# Communication.net
KiCad netlist of a schematic drawn in Altium Designer
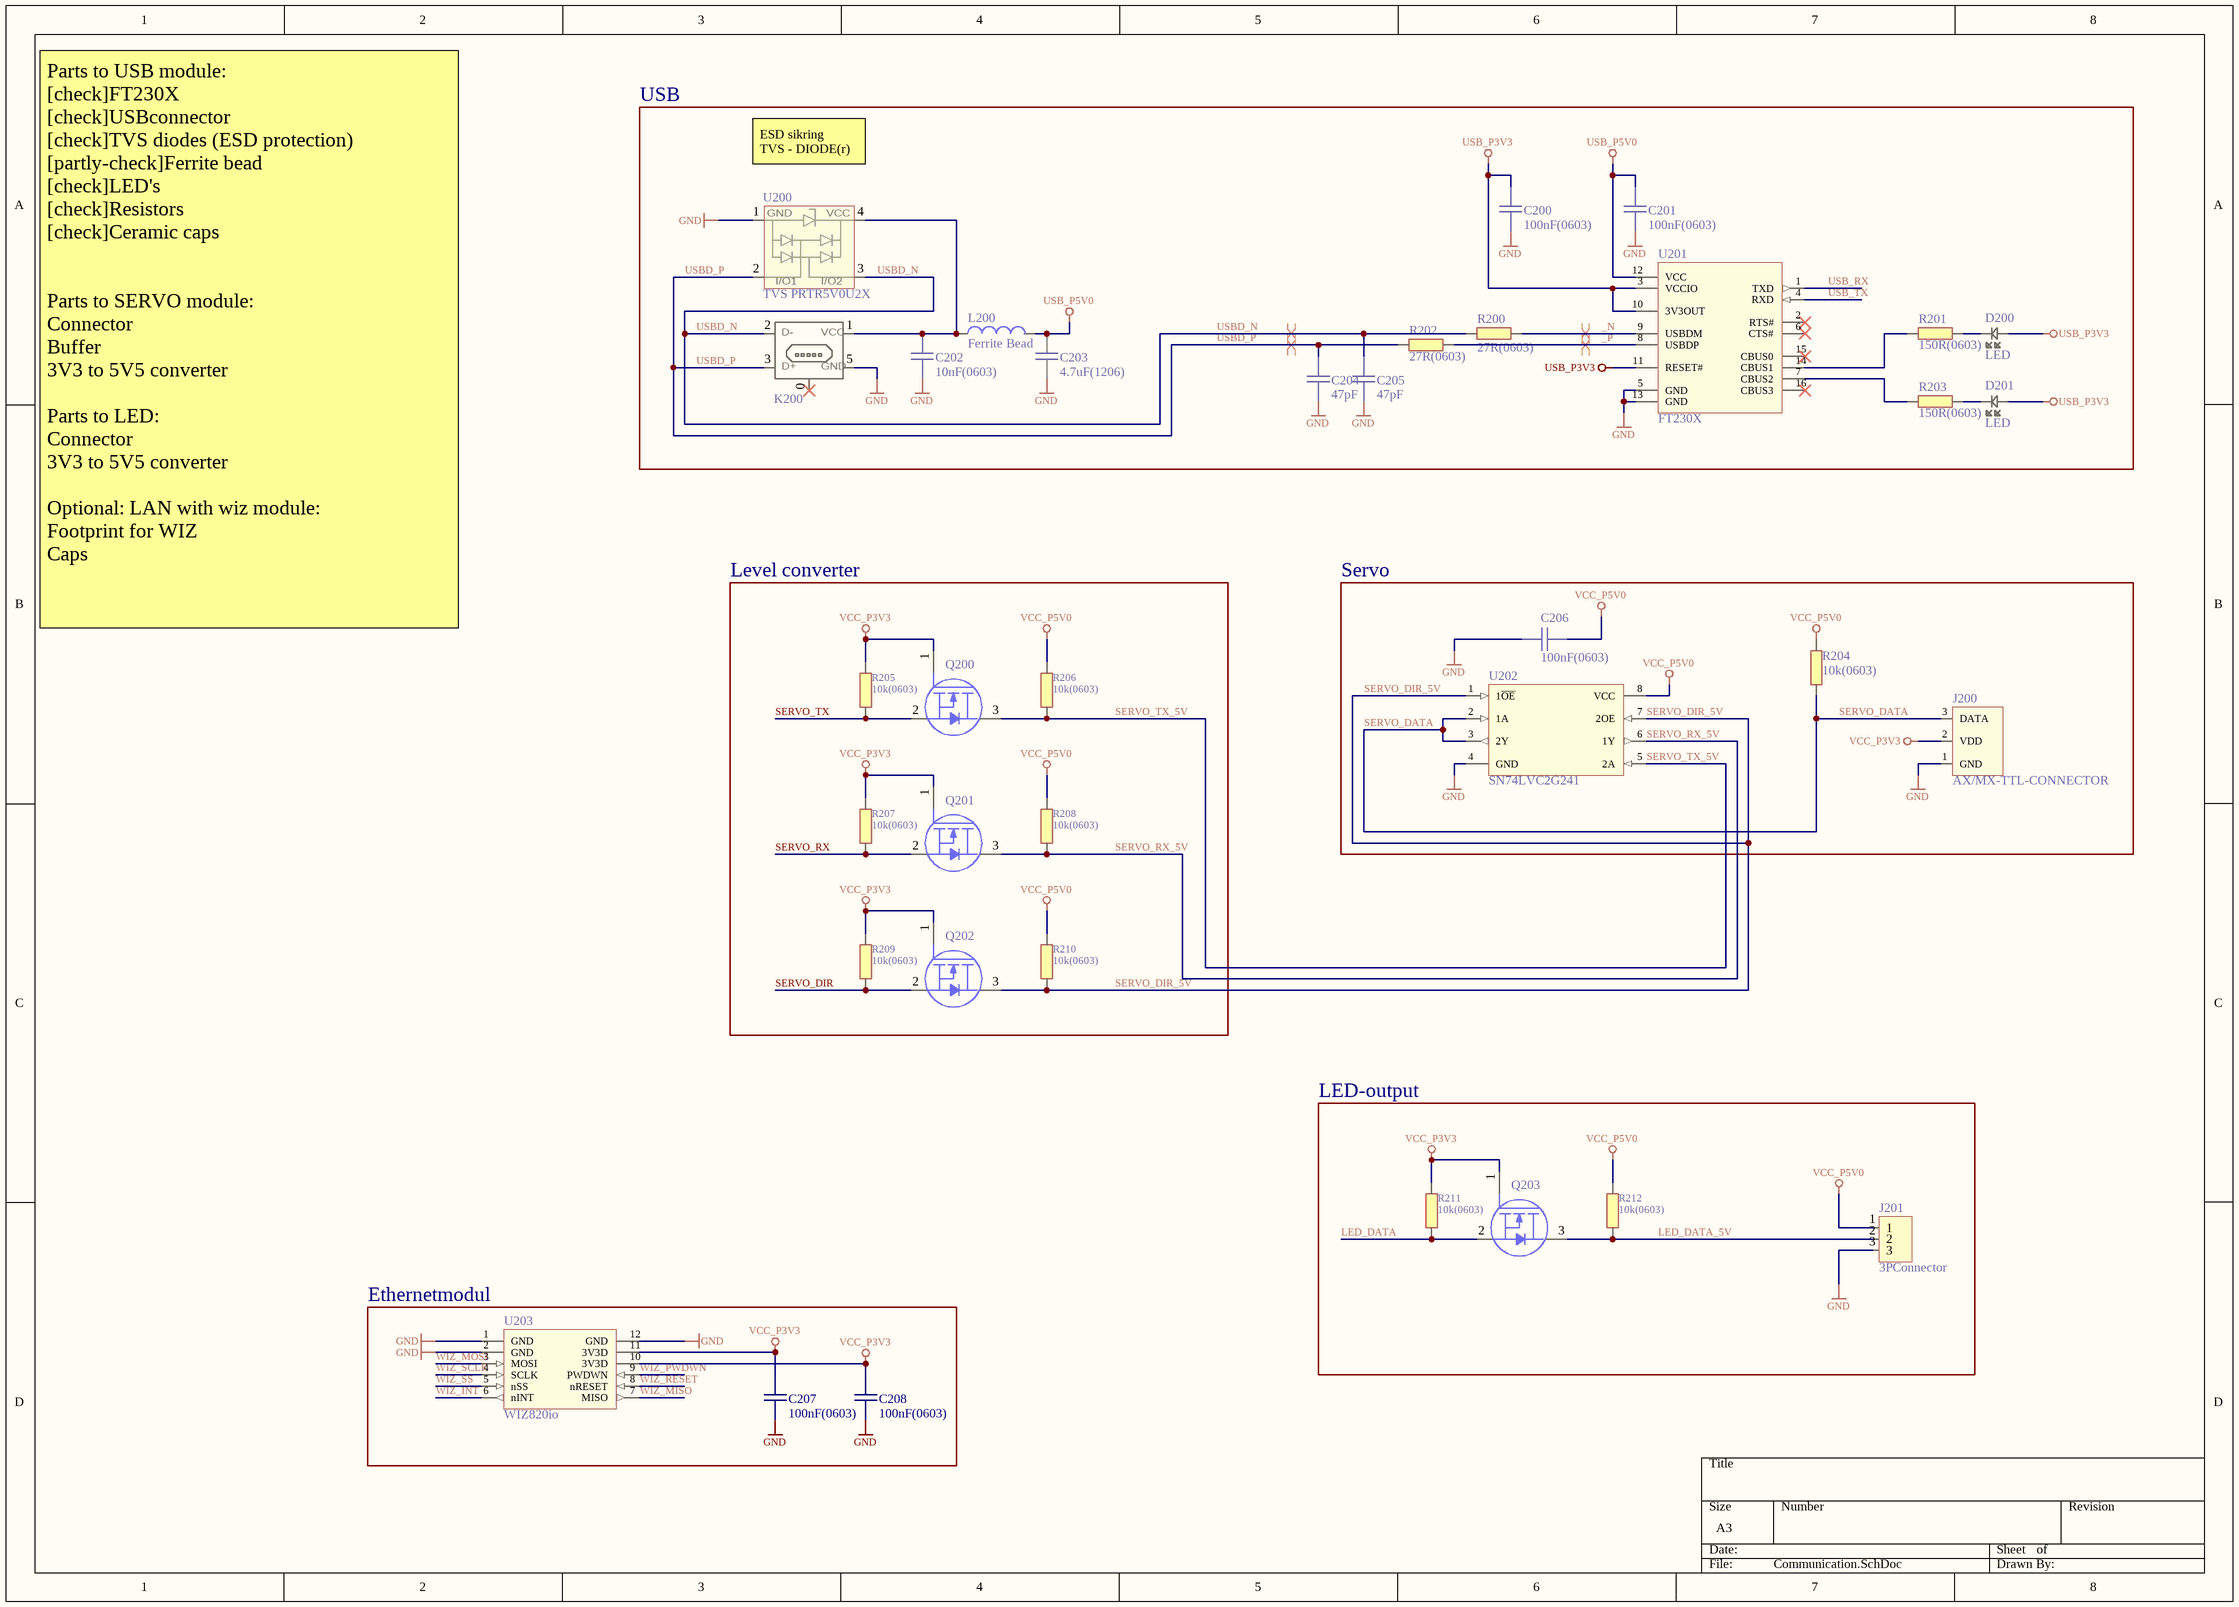
[diagram p0: Communication.SchDoc]

(export (version "E")
  (design (tool "Eeschema 10.0.6"))
  (components
    (comp (ref "C200")
      (value "100nF(0603)")
      (footprint "CAPC0603(1608)55_N")
      (description "100nF 0603 5% X7R 50V")
      (libsource (lib "OVLib") (part "CAP"))
    )
    (comp (ref "C201")
      (value "100nF(0603)")
      (footprint "CAPC0603(1608)55_N")
      (description "100nF 0603 5% X7R 50V")
      (libsource (lib "OVLib") (part "CAP"))
    )
    (comp (ref "C202")
      (value "10nF(0603)")
      (footprint "CAPC0603(1608)55_N")
      (description "0603 5% NP0 50V")
      (libsource (lib "OVLib") (part "CAP"))
    )
    (comp (ref "C203")
      (value "4.7uF(1206)")
      (footprint "CAPC1206(3216)170_N")
      (description "1206 chip X7R 50V")
      (libsource (lib "OVLib") (part "CAP"))
    )
    (comp (ref "C204")
      (value "47pF")
      (footprint "CAPC0603(1608)55_N")
      (description "0603 5% NP0 50V")
      (libsource (lib "OVLib") (part "CAP"))
    )
    (comp (ref "C205")
      (value "47pF")
      (footprint "CAPC0603(1608)55_N")
      (description "0603 5% NP0 50V")
      (libsource (lib "OVLib") (part "CAP"))
    )
    (comp (ref "C206")
      (value "100nF(0603)")
      (footprint "CAPC0603(1608)55_N")
      (description "100nF 0603 5% X7R 50V")
      (libsource (lib "OVLib") (part "CAP"))
    )
    (comp (ref "C207")
      (value "100nF(0603)")
      (footprint "CAPC0603(1608)55_N")
      (description "100nF 0603 5% X7R 50V")
      (libsource (lib "OVLib") (part "CAP"))
    )
    (comp (ref "C208")
      (value "100nF(0603)")
      (footprint "CAPC0603(1608)55_N")
      (description "100nF 0603 5% X7R 50V")
      (libsource (lib "OVLib") (part "CAP"))
    )
    (comp (ref "D200")
      (value "LED")
      (footprint "I_LEDC0603(1608)_N")
      (description "SMD")
      (libsource (lib "OVLib") (part "LED"))
    )
    (comp (ref "D201")
      (value "LED")
      (footprint "I_LEDC0603(1608)_N")
      (description "SMD")
      (libsource (lib "OVLib") (part "LED"))
    )
    (comp (ref "J200")
      (value "AX/MX-TTL-CONNECTOR")
      (footprint "MOLEX_22-03-5035")
      (description "Dynamixel AX/MX-Series servo connector 3 pin TTL version")
      (fields (field (name "MPN") "22-03-5035"))
      (libsource (lib "AX_MX-TTL-CONNECTOR") (part "AX/MX-TTL-CONNECTOR"))
    )
    (comp (ref "J201")
      (value "3PConnector")
      (footprint "JST_3P")
      (description "pris pr. stk.")
      (libsource (lib "OVLib") (part "3PConnector"))
    )
    (comp (ref "K200")
      (value "USB-OTG")
      (footprint "MILL-MAX_897-43-005-00-100001")
      (description "MINI USB B DEVICE CONNECTOR MOLEX 51387-0571")
      (fields
        (field (name "MANUFACTURER") "Mill-Max Manufacturing Corp.")
        (field (name "MPN") "897-43-005-00-100001")
      )
      (libsource (lib "MILL-MAX_897-43-005-00-100001") (part "MILL-MAX_897-43-005-00-100001"))
    )
    (comp (ref "L200")
      (value "Ferrite Bead")
      (footprint "0603")
      (description "Ferrite Bead 0603")
      (fields (field (name "MPN") "BLM18SG331TN1D"))
      (libsource (lib "BLM18SG331TN1D") (part "BLM18SG331TN1D"))
    )
    (comp (ref "Q200")
      (value "MOSFET_N_GSD")
      (footprint "SOT323P130X100-3_N")
      (description "N-Channel MOSFET 300mA")
      (libsource (lib "OVLib") (part "MOSFET_N_GSD"))
    )
    (comp (ref "Q201")
      (value "MOSFET_N_GSD")
      (footprint "SOT323P130X100-3_N")
      (description "N-Channel MOSFET 300mA")
      (libsource (lib "OVLib") (part "MOSFET_N_GSD"))
    )
    (comp (ref "Q202")
      (value "MOSFET_N_GSD")
      (footprint "SOT323P130X100-3_N")
      (description "N-Channel MOSFET 300mA")
      (libsource (lib "OVLib") (part "MOSFET_N_GSD"))
    )
    (comp (ref "Q203")
      (value "MOSFET_N_GSD")
      (footprint "SOT323P130X100-3_N")
      (description "N-Channel MOSFET 300mA")
      (libsource (lib "OVLib") (part "MOSFET_N_GSD"))
    )
    (comp (ref "R200")
      (value "27R(0603)")
      (footprint "RESC0603(1608)_N")
      (description "0603 0.1W 1% Thick film resistor")
      (libsource (lib "") (part "Resistor2_3"))
    )
    (comp (ref "R201")
      (value "150R(0603)")
      (footprint "RESC0603(1608)_N")
      (description "0603 0.1W 1% Thick film resistor")
      (libsource (lib "") (part "Resistor2_1"))
    )
    (comp (ref "R202")
      (value "27R(0603)")
      (footprint "RESC0603(1608)_N")
      (description "0603 0.1W 1% Thick film resistor")
      (libsource (lib "") (part "Resistor2_3"))
    )
    (comp (ref "R203")
      (value "150R(0603)")
      (footprint "RESC0603(1608)_N")
      (description "0603 0.1W 1% Thick film resistor")
      (libsource (lib "") (part "Resistor2_1"))
    )
    (comp (ref "R204")
      (value "10k(0603)")
      (footprint "RESC0603(1608)_N")
      (description "10k 0603 0.1W 1% Thick film resistor")
      (libsource (lib "") (part "Resistor2_2"))
    )
    (comp (ref "R205")
      (value "10k(0603)")
      (footprint "RESC0603(1608)_N")
      (description "10k 0603 0.1W 1% Thick film resistor")
      (libsource (lib "OVLib") (part "Resistor2"))
    )
    (comp (ref "R206")
      (value "10k(0603)")
      (footprint "RESC0603(1608)_N")
      (description "10k 0603 0.1W 1% Thick film resistor")
      (libsource (lib "OVLib") (part "Resistor2"))
    )
    (comp (ref "R207")
      (value "10k(0603)")
      (footprint "RESC0603(1608)_N")
      (description "10k 0603 0.1W 1% Thick film resistor")
      (libsource (lib "OVLib") (part "Resistor2"))
    )
    (comp (ref "R208")
      (value "10k(0603)")
      (footprint "RESC0603(1608)_N")
      (description "10k 0603 0.1W 1% Thick film resistor")
      (libsource (lib "OVLib") (part "Resistor2"))
    )
    (comp (ref "R209")
      (value "10k(0603)")
      (footprint "RESC0603(1608)_N")
      (description "10k 0603 0.1W 1% Thick film resistor")
      (libsource (lib "OVLib") (part "Resistor2"))
    )
    (comp (ref "R210")
      (value "10k(0603)")
      (footprint "RESC0603(1608)_N")
      (description "10k 0603 0.1W 1% Thick film resistor")
      (libsource (lib "OVLib") (part "Resistor2"))
    )
    (comp (ref "R211")
      (value "10k(0603)")
      (footprint "RESC0603(1608)_N")
      (description "10k 0603 0.1W 1% Thick film resistor")
      (libsource (lib "OVLib") (part "Resistor2"))
    )
    (comp (ref "R212")
      (value "10k(0603)")
      (footprint "RESC0603(1608)_N")
      (description "10k 0603 0.1W 1% Thick film resistor")
      (libsource (lib "OVLib") (part "Resistor2"))
    )
    (comp (ref "U200")
      (value "TVS PRTR5V0U2X")
      (footprint "SOT143B-M")
      (description "TVS Didode dual PRTR5V0U2X")
      (fields (field (name "MPN") "PRTR5V0U2X") (field (name "MANUFACTURER") "NXP"))
      (libsource (lib "PRTR5V0U2X") (part "PRTR5V0U2X"))
    )
    (comp (ref "U201")
      (value "FT230X")
      (footprint "SOP0635P4800-16N")
      (description "IC USB SERIAL BASIC UART 16SSOP")
      (fields
        (field (name "MPN") "FT230XS-R")
        (field (name "MANUFACTURER") "FTDI, Future Technology Devices International Ltd")
      )
      (libsource (lib "FT230XS") (part "FT230X"))
    )
    (comp (ref "U202")
      (value "SN74LVC2G241")
      (footprint "TSOP65P400X130-8N")
      (description "Dual  Buffer/Driver  With  3-State  Outputs, designed for 1.65-5.5Vcc operation")
      (fields (field (name "MANUFACTURER") "Texas Instruments") (field (name "MPN") "SN74LVC2G241DCUR"))
      (libsource (lib "SN74LVC2G241") (part "SN74LVC2G241"))
    )
    (comp (ref "U203")
      (value "WIZ820io")
      (footprint "Wiz820io")
      (description "WIZ820io, Ethernet module with W5200 module onboard and MAG-JACK")
      (fields (field (name "MPN") "WIZ820IO") (field (name "MANUFACTURER") "WIZnet"))
      (libsource (lib "WIZ820io") (part "WIZ820io"))
    )
  )
  (nets
    (net (code "1") (name "/LED_DATA") (class "Default")
      (node (ref "Q203") (pin "2") (pinfunction "Source_2") (pintype "passive"))
      (node (ref "R211") (pin "2") (pinfunction "2_2") (pintype "passive"))
    )
    (net (code "2") (name "/LED_DATA_5V") (class "Default")
      (node (ref "J201") (pin "2") (pinfunction "2_2") (pintype "passive"))
      (node (ref "Q203") (pin "3") (pinfunction "Drain_3") (pintype "passive"))
      (node (ref "R212") (pin "2") (pinfunction "2_2") (pintype "passive"))
    )
    (net (code "3") (name "/SERVO_DATA") (class "Default")
      (node (ref "J200") (pin "3") (pinfunction "DATA_3") (pintype "passive"))
      (node (ref "R204") (pin "1") (pinfunction "1_1") (pintype "passive"))
      (node (ref "U202") (pin "2") (pinfunction "1A_2") (pintype "input"))
      (node (ref "U202") (pin "3") (pinfunction "2Y_3") (pintype "output"))
    )
    (net (code "4") (name "/SERVO_DIR") (class "Default")
      (node (ref "Q202") (pin "2") (pinfunction "Source_2") (pintype "passive"))
      (node (ref "R209") (pin "2") (pinfunction "2_2") (pintype "passive"))
    )
    (net (code "5") (name "/SERVO_DIR_5V") (class "Default")
      (node (ref "Q202") (pin "3") (pinfunction "Drain_3") (pintype "passive"))
      (node (ref "R210") (pin "2") (pinfunction "2_2") (pintype "passive"))
      (node (ref "U202") (pin "1") (pinfunction "1~{OE}_1") (pintype "input"))
      (node (ref "U202") (pin "7") (pinfunction "2OE_7") (pintype "input"))
    )
    (net (code "6") (name "/SERVO_RX") (class "Default")
      (node (ref "Q201") (pin "2") (pinfunction "Source_2") (pintype "passive"))
      (node (ref "R207") (pin "2") (pinfunction "2_2") (pintype "passive"))
    )
    (net (code "7") (name "/SERVO_RX_5V") (class "Default")
      (node (ref "Q201") (pin "3") (pinfunction "Drain_3") (pintype "passive"))
      (node (ref "R208") (pin "2") (pinfunction "2_2") (pintype "passive"))
      (node (ref "U202") (pin "6") (pinfunction "1Y_6") (pintype "output"))
    )
    (net (code "8") (name "/SERVO_TX") (class "Default")
      (node (ref "Q200") (pin "2") (pinfunction "Source_2") (pintype "passive"))
      (node (ref "R205") (pin "2") (pinfunction "2_2") (pintype "passive"))
    )
    (net (code "9") (name "/SERVO_TX_5V") (class "Default")
      (node (ref "Q200") (pin "3") (pinfunction "Drain_3") (pintype "passive"))
      (node (ref "R206") (pin "2") (pinfunction "2_2") (pintype "passive"))
      (node (ref "U202") (pin "5") (pinfunction "2A_5") (pintype "input"))
    )
    (net (code "10") (name "/USBD_N") (class "Default")
      (node (ref "C205") (pin "2") (pinfunction "2_2") (pintype "passive"))
      (node (ref "K200") (pin "2") (pinfunction "D-_2") (pintype "passive"))
      (node (ref "R200") (pin "1") (pinfunction "1_1") (pintype "passive"))
      (node (ref "U200") (pin "3") (pinfunction "I/O2_3") (pintype "passive"))
    )
    (net (code "11") (name "/USBD_P") (class "Default")
      (node (ref "C204") (pin "2") (pinfunction "2_2") (pintype "passive"))
      (node (ref "K200") (pin "3") (pinfunction "D+_3") (pintype "passive"))
      (node (ref "R202") (pin "1") (pinfunction "1_1") (pintype "passive"))
      (node (ref "U200") (pin "2") (pinfunction "I/O1_2") (pintype "passive"))
    )
    (net (code "12") (name "/USB_RX") (class "Default")
      (node (ref "U201") (pin "1") (pinfunction "TXD_1") (pintype "output"))
    )
    (net (code "13") (name "/USB_TX") (class "Default")
      (node (ref "U201") (pin "4") (pinfunction "RXD_4") (pintype "input"))
    )
    (net (code "14") (name "/WIZ_INT") (class "Default")
      (node (ref "U203") (pin "6") (pinfunction "nINT_6") (pintype "output"))
    )
    (net (code "15") (name "/WIZ_MISO") (class "Default")
      (node (ref "U203") (pin "7") (pinfunction "MISO_7") (pintype "output"))
    )
    (net (code "16") (name "/WIZ_MOSI") (class "Default")
      (node (ref "U203") (pin "3") (pinfunction "MOSI_3") (pintype "input"))
    )
    (net (code "17") (name "/WIZ_PWDWN") (class "Default")
      (node (ref "U203") (pin "9") (pinfunction "PWDWN_9") (pintype "input"))
    )
    (net (code "18") (name "/WIZ_RESET") (class "Default")
      (node (ref "U203") (pin "8") (pinfunction "nRESET_8") (pintype "input"))
    )
    (net (code "19") (name "/WIZ_SCLK") (class "Default")
      (node (ref "U203") (pin "4") (pinfunction "SCLK_4") (pintype "input"))
    )
    (net (code "20") (name "/WIZ_SS") (class "Default")
      (node (ref "U203") (pin "5") (pinfunction "nSS_5") (pintype "input"))
    )
    (net (code "21") (name "/_N") (class "Default")
      (node (ref "R200") (pin "2") (pinfunction "2_2") (pintype "passive"))
      (node (ref "U201") (pin "9") (pinfunction "USBDM_9") (pintype "passive"))
    )
    (net (code "22") (name "/_P") (class "Default")
      (node (ref "R202") (pin "2") (pinfunction "2_2") (pintype "passive"))
      (node (ref "U201") (pin "8") (pinfunction "USBDP_8") (pintype "passive"))
    )
    (net (code "23") (name "GND") (class "Default")
      (node (ref "C200") (pin "1") (pinfunction "1_1") (pintype "passive"))
      (node (ref "C201") (pin "1") (pinfunction "1_1") (pintype "passive"))
      (node (ref "C202") (pin "1") (pinfunction "1_1") (pintype "passive"))
      (node (ref "C203") (pin "1") (pinfunction "1_1") (pintype "passive"))
      (node (ref "C204") (pin "1") (pinfunction "1_1") (pintype "passive"))
      (node (ref "C205") (pin "1") (pinfunction "1_1") (pintype "passive"))
      (node (ref "C206") (pin "1") (pinfunction "1_1") (pintype "passive"))
      (node (ref "C207") (pin "1") (pinfunction "1_1") (pintype "passive"))
      (node (ref "C208") (pin "1") (pinfunction "1_1") (pintype "passive"))
      (node (ref "J200") (pin "1") (pinfunction "GND_1") (pintype "passive"))
      (node (ref "J201") (pin "3") (pinfunction "3_3") (pintype "passive"))
      (node (ref "K200") (pin "5") (pinfunction "GD_5") (pintype "passive"))
      (node (ref "U200") (pin "1") (pinfunction "GND_1") (pintype "passive"))
      (node (ref "U201") (pin "13") (pinfunction "GND_13") (pintype "passive"))
      (node (ref "U201") (pin "5") (pinfunction "GND_5") (pintype "passive"))
      (node (ref "U202") (pin "4") (pinfunction "GND_4") (pintype "power_in"))
      (node (ref "U203") (pin "1") (pinfunction "GND_1") (pintype "passive"))
      (node (ref "U203") (pin "12") (pinfunction "GND_12") (pintype "passive"))
      (node (ref "U203") (pin "2") (pinfunction "GND_2") (pintype "passive"))
    )
    (net (code "24") (name "Net-(D200-Pad2)") (class "Default")
      (node (ref "D200") (pin "2") (pinfunction "2_2") (pintype "passive"))
      (node (ref "R201") (pin "1") (pinfunction "1_1") (pintype "passive"))
    )
    (net (code "25") (name "Net-(D201-Pad2)") (class "Default")
      (node (ref "D201") (pin "2") (pinfunction "2_2") (pintype "passive"))
      (node (ref "R203") (pin "1") (pinfunction "1_1") (pintype "passive"))
    )
    (net (code "26") (name "Net-(K200-VB)") (class "Default")
      (node (ref "C202") (pin "2") (pinfunction "2_2") (pintype "passive"))
      (node (ref "K200") (pin "1") (pinfunction "VB_1") (pintype "passive"))
      (node (ref "L200") (pin "1") (pintype "passive"))
      (node (ref "U200") (pin "4") (pinfunction "VCC_4") (pintype "passive"))
    )
    (net (code "27") (name "Net-(U201-CBUS1)") (class "Default")
      (node (ref "R201") (pin "2") (pinfunction "2_2") (pintype "passive"))
      (node (ref "U201") (pin "14") (pinfunction "CBUS1_14") (pintype "passive"))
    )
    (net (code "28") (name "Net-(U201-CBUS2)") (class "Default")
      (node (ref "R203") (pin "2") (pinfunction "2_2") (pintype "passive"))
      (node (ref "U201") (pin "7") (pinfunction "CBUS2_7") (pintype "passive"))
    )
    (net (code "29") (name "USB_P3V3") (class "Default")
      (node (ref "C200") (pin "2") (pinfunction "2_2") (pintype "passive"))
      (node (ref "D200") (pin "1") (pinfunction "1_1") (pintype "passive"))
      (node (ref "D201") (pin "1") (pinfunction "1_1") (pintype "passive"))
      (node (ref "U201") (pin "10") (pinfunction "3V3OUT_10") (pintype "passive"))
      (node (ref "U201") (pin "11") (pinfunction "RESET#_11") (pintype "passive"))
      (node (ref "U201") (pin "3") (pinfunction "VCCIO_3") (pintype "passive"))
    )
    (net (code "30") (name "USB_P5V0") (class "Default")
      (node (ref "C201") (pin "2") (pinfunction "2_2") (pintype "passive"))
      (node (ref "C203") (pin "2") (pinfunction "2_2") (pintype "passive"))
      (node (ref "L200") (pin "2") (pintype "passive"))
      (node (ref "U201") (pin "12") (pinfunction "VCC_12") (pintype "passive"))
    )
    (net (code "31") (name "VCC_P3V3") (class "Default")
      (node (ref "C207") (pin "2") (pinfunction "2_2") (pintype "passive"))
      (node (ref "C208") (pin "2") (pinfunction "2_2") (pintype "passive"))
      (node (ref "J200") (pin "2") (pinfunction "VDD_2") (pintype "passive"))
      (node (ref "Q200") (pin "1") (pinfunction "Gate_1") (pintype "passive"))
      (node (ref "Q201") (pin "1") (pinfunction "Gate_1") (pintype "passive"))
      (node (ref "Q202") (pin "1") (pinfunction "Gate_1") (pintype "passive"))
      (node (ref "Q203") (pin "1") (pinfunction "Gate_1") (pintype "passive"))
      (node (ref "R205") (pin "1") (pinfunction "1_1") (pintype "passive"))
      (node (ref "R207") (pin "1") (pinfunction "1_1") (pintype "passive"))
      (node (ref "R209") (pin "1") (pinfunction "1_1") (pintype "passive"))
      (node (ref "R211") (pin "1") (pinfunction "1_1") (pintype "passive"))
      (node (ref "U203") (pin "10") (pinfunction "3V3D_10") (pintype "passive"))
      (node (ref "U203") (pin "11") (pinfunction "3V3D_11") (pintype "passive"))
    )
    (net (code "32") (name "VCC_P5V0") (class "Default")
      (node (ref "C206") (pin "2") (pinfunction "2_2") (pintype "passive"))
      (node (ref "J201") (pin "1") (pinfunction "1_1") (pintype "passive"))
      (node (ref "R204") (pin "2") (pinfunction "2_2") (pintype "passive"))
      (node (ref "R206") (pin "1") (pinfunction "1_1") (pintype "passive"))
      (node (ref "R208") (pin "1") (pinfunction "1_1") (pintype "passive"))
      (node (ref "R210") (pin "1") (pinfunction "1_1") (pintype "passive"))
      (node (ref "R212") (pin "1") (pinfunction "1_1") (pintype "passive"))
      (node (ref "U202") (pin "8") (pinfunction "VCC_8") (pintype "power_in"))
    )
    (net (code "33") (name "unconnected-(K200-Shield-Pad0)") (class "Default")
      (node (ref "K200") (pin "0") (pinfunction "Shield_0") (pintype "passive+no_connect"))
    )
    (net (code "34") (name "unconnected-(U201-CBUS0-Pad15)") (class "Default")
      (node (ref "U201") (pin "15") (pinfunction "CBUS0_15") (pintype "passive+no_connect"))
    )
    (net (code "35") (name "unconnected-(U201-CBUS3-Pad16)") (class "Default")
      (node (ref "U201") (pin "16") (pinfunction "CBUS3_16") (pintype "passive+no_connect"))
    )
    (net (code "36") (name "unconnected-(U201-CTS#-Pad6)") (class "Default")
      (node (ref "U201") (pin "6") (pinfunction "CTS#_6") (pintype "passive+no_connect"))
    )
    (net (code "37") (name "unconnected-(U201-RTS#-Pad2)") (class "Default")
      (node (ref "U201") (pin "2") (pinfunction "RTS#_2") (pintype "passive+no_connect"))
    )
  )
)
